# Voeding.net
KiCad netlist of a schematic drawn in Altium Designer
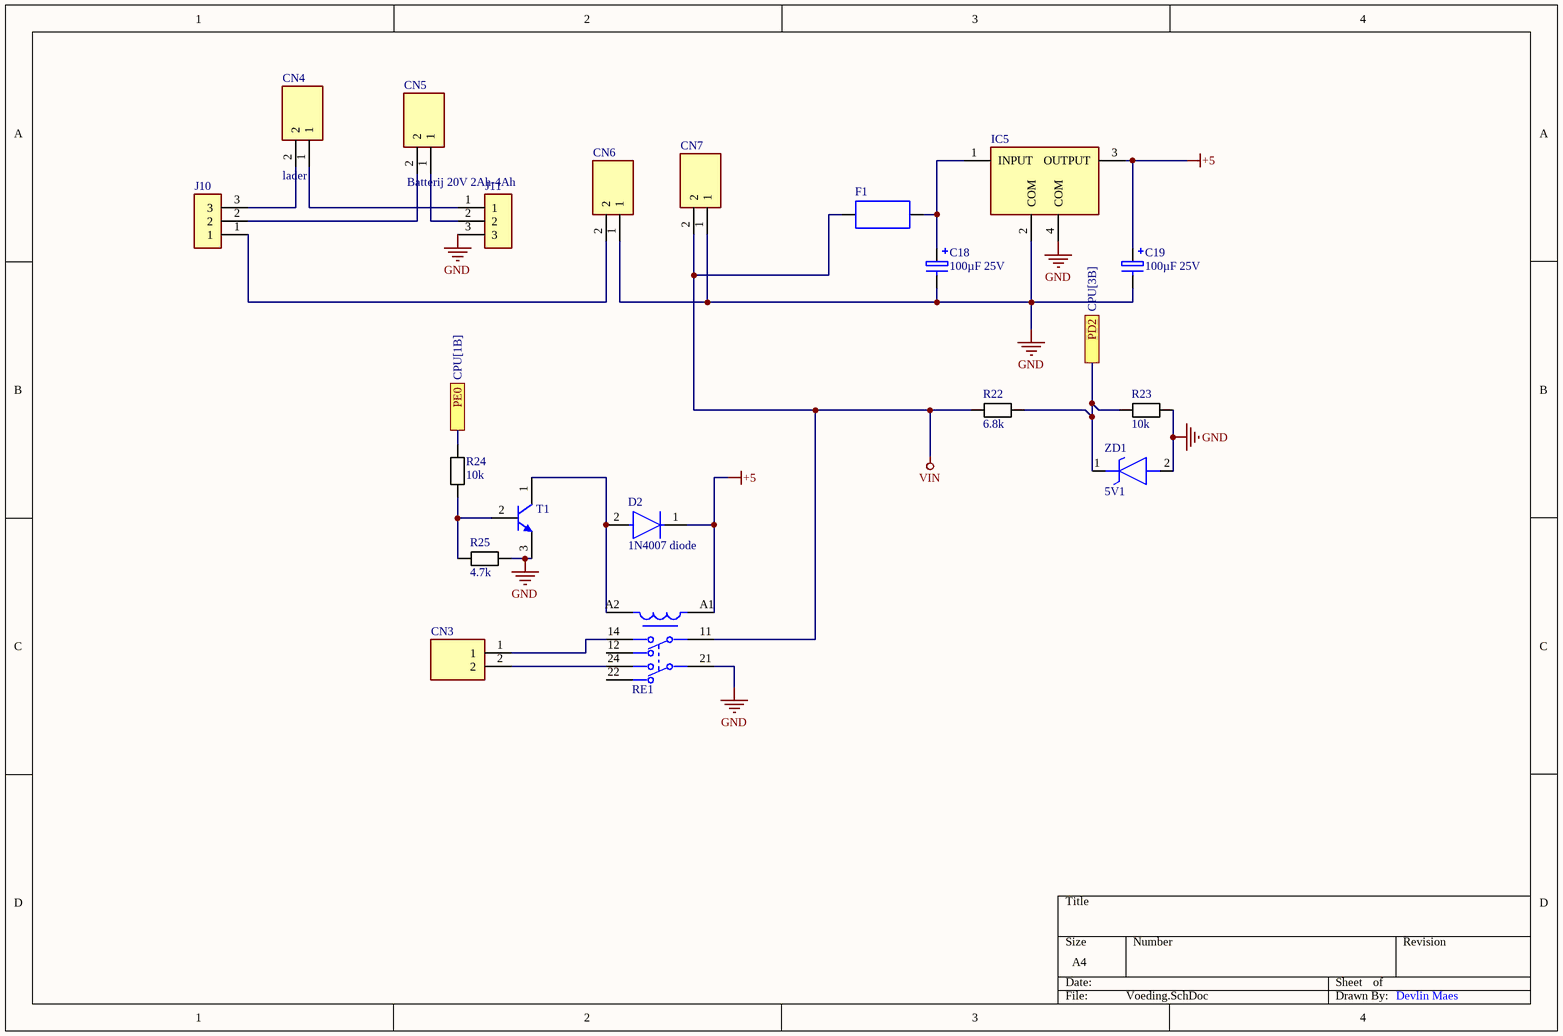
[diagram p0: Voeding.SchDoc]

(export (version "E")
  (design (tool "Eeschema 10.0.6"))
  (components
    (comp (ref "C18")
      (value "100µF 25V")
      (footprint "Elco 100uF 25V")
      (fields
        (field (name "PART NUMBER") "02015A270JAT2A")
        (field (name "MANUFACTURER") "AVX Interconnect / Elco")
      )
      (libsource (lib "schoolprojectcomponentlib") (part "Condensator Elco"))
    )
    (comp (ref "C19")
      (value "100µF 25V")
      (footprint "Elco 100uF 25V")
      (fields
        (field (name "PART NUMBER") "02015A270JAT2A")
        (field (name "MANUFACTURER") "AVX Interconnect / Elco")
      )
      (libsource (lib "schoolprojectcomponentlib") (part "Condensator Elco"))
    )
    (comp (ref "CN3")
      (value "282836-2")
      (footprint "Schroefconnector 2 Pin - duplicate")
      (description "Connector")
      (libsource (lib "schoolprojectcomponentlib") (part "Schroefconnector 2 Pin L"))
    )
    (comp (ref "CN4")
      (value "lader")
      (footprint "Schroefconnector 2 Pin - duplicate")
      (description "Connector")
      (fields (field (name "MANUFACTURER_PART_NUMBER") "282836-2"))
      (libsource (lib "") (part "Schroefconnector 2 Pin L_1"))
    )
    (comp (ref "CN5")
      (value "Batterij 20V 2Ah-4Ah")
      (footprint "Schroefconnector 2 Pin - duplicate")
      (description "Connector")
      (fields (field (name "MANUFACTURER_PART_NUMBER") "282836-2"))
      (libsource (lib "") (part "Schroefconnector 2 Pin L_1"))
    )
    (comp (ref "CN6")
      (value "282836-2")
      (footprint "Schroefconnector 2 Pin - duplicate")
      (description "Connector")
      (libsource (lib "") (part "Schroefconnector 2 Pin L_1"))
    )
    (comp (ref "CN7")
      (value "282836-2")
      (footprint "Schroefconnector 2 Pin - duplicate")
      (description "Connector")
      (libsource (lib "") (part "Schroefconnector 2 Pin L_1"))
    )
    (comp (ref "D2")
      (value "1N4007 diode")
      (footprint "1N4007(diode)")
      (description "Rectifier diode 1000 V 1 A DO-41, ,")
      (fields (field (name "MANUFACTURER PART NUMBER") "1N4007") (field (name "MANUFACTURER") "Diotec"))
      (libsource (lib "schoolprojectcomponentlib") (part "1N4007 diode"))
    )
    (comp (ref "F1")
      (value "~")
      (footprint "FuseHolder")
      (libsource (lib "schoolprojectcomponentlib") (part "FuseHolder"))
    )
    (comp (ref "IC5")
      (value "TL780-05CKTTR")
      (footprint "DC-DC Convertor")
      (description "IC REG LIN 5V 1.5A DDPAK/TO263-3")
      (libsource (lib "schoolprojectcomponentlib") (part "DC/DC Convertor"))
    )
    (comp (ref "J10")
      (value "5-146280-3")
      (footprint "3 Pin Header")
      (description "Connector 5-146280-3")
      (fields (field (name "MOUSER2 PART NUMBER") "571-5-146280-3"))
      (libsource (lib "schoolprojectcomponentlib") (part "3 Pin Header R"))
    )
    (comp (ref "J11")
      (value "5-146280-3")
      (footprint "3 Pin Header")
      (description "Connector 5-146280-3")
      (fields (field (name "MOUSER2 PART NUMBER") "571-5-146280-3"))
      (libsource (lib "") (part "3 Pin Header R_1"))
    )
    (comp (ref "R22")
      (value "6.8k")
      (footprint "weerstand")
      (fields (field (name "MANUFACTURER") "Vishay Dale") (field (name "PART NUMBER") "CRCW08050000Z0EA"))
      (libsource (lib "schoolprojectcomponentlib") (part "weerstand"))
    )
    (comp (ref "R23")
      (value "10k")
      (footprint "weerstand")
      (fields (field (name "MANUFACTURER") "Vishay Dale") (field (name "PART NUMBER") "CRCW08050000Z0EA"))
      (libsource (lib "schoolprojectcomponentlib") (part "weerstand"))
    )
    (comp (ref "R24")
      (value "10k")
      (footprint "weerstand")
      (fields (field (name "MANUFACTURER") "Vishay Dale") (field (name "PART NUMBER") "CRCW08050000Z0EA"))
      (libsource (lib "schoolprojectcomponentlib") (part "weerstand"))
    )
    (comp (ref "R25")
      (value "4.7k")
      (footprint "weerstand")
      (fields (field (name "MANUFACTURER") "Vishay Dale") (field (name "PART NUMBER") "CRCW08050000Z0EA"))
      (libsource (lib "schoolprojectcomponentlib") (part "weerstand"))
    )
    (comp (ref "RE1")
      (value "RT424005")
      (footprint "Relay RT424005")
      (description "RELAY GENERAL PURPOSE DPDT 8A 5V")
      (fields
        (field (name "OCTOPART") "https://octopart.com/5-1393243-9-te+connectivity-41835766")
        (field (name "MANUFACTURER") "TE Connectivity")
      )
      (libsource (lib "schoolprojectcomponentlib") (part "Relay"))
    )
    (comp (ref "T1")
      (value "BC547C")
      (footprint "BC547C (transistor)")
      (description "Amplifier Transistor, NPN Silicon, 3-Pin, 0,1A TO-92, Bulk Box")
      (fields (field (name "MANUFACTURER") "On Semiconductor"))
      (libsource (lib "schoolprojectcomponentlib") (part "BC547C"))
    )
    (comp (ref "ZD1")
      (value "5V1")
      (footprint "Zener diode")
      (description "Zener Diode")
      (fields
        (field (name "MOUSER2 PART NUMBER") "512-1N5231CTR")
        (field (name "MANUFACTURER_PART_NUMBER") "1N5231CTR")
      )
      (libsource (lib "schoolprojectcomponentlib") (part "Zenerdiode"))
    )
  )
  (nets
    (net (code "1") (name "+5") (class "Default")
      (node (ref "C19") (pin "1") (pinfunction "1_1") (pintype "passive"))
      (node (ref "D2") (pin "1") (pinfunction "C_1") (pintype "passive"))
      (node (ref "IC5") (pin "3") (pinfunction "OUTPUT_3") (pintype "power_in"))
      (node (ref "RE1") (pin "A1") (pinfunction "A1_A1") (pintype "passive"))
    )
    (net (code "2") (name "/PD2") (class "Default")
      (node (ref "R22") (pin "1") (pinfunction "1_1") (pintype "passive"))
      (node (ref "R23") (pin "2") (pinfunction "2_2") (pintype "passive"))
      (node (ref "ZD1") (pin "1") (pinfunction "K_1") (pintype "passive"))
    )
    (net (code "3") (name "/PE0") (class "Default")
      (node (ref "R24") (pin "2") (pinfunction "2_2") (pintype "passive"))
    )
    (net (code "4") (name "GND") (class "Default")
      (node (ref "C18") (pin "2") (pinfunction "2_2") (pintype "passive"))
      (node (ref "C19") (pin "2") (pinfunction "2_2") (pintype "passive"))
      (node (ref "CN6") (pin "1") (pinfunction "1_1") (pintype "passive"))
      (node (ref "CN7") (pin "1") (pinfunction "1_1") (pintype "passive"))
      (node (ref "IC5") (pin "2") (pinfunction "COM_2") (pintype "passive"))
      (node (ref "IC5") (pin "4") (pinfunction "COM_4") (pintype "passive"))
      (node (ref "J11") (pin "3") (pinfunction "3_3") (pintype "passive"))
      (node (ref "R23") (pin "1") (pinfunction "1_1") (pintype "passive"))
      (node (ref "R25") (pin "1") (pinfunction "1_1") (pintype "passive"))
      (node (ref "RE1") (pin "21") (pinfunction "21_21") (pintype "passive"))
      (node (ref "T1") (pin "3") (pinfunction "E_3") (pintype "passive"))
      (node (ref "ZD1") (pin "2") (pinfunction "A_2") (pintype "passive"))
    )
    (net (code "5") (name "Net-(CN3-Pad1)") (class "Default")
      (node (ref "CN3") (pin "1") (pinfunction "1_1") (pintype "passive"))
      (node (ref "RE1") (pin "14") (pinfunction "14_14") (pintype "passive"))
    )
    (net (code "6") (name "Net-(CN3-Pad2)") (class "Default")
      (node (ref "CN3") (pin "2") (pinfunction "2_2") (pintype "passive"))
      (node (ref "RE1") (pin "24") (pinfunction "24_24") (pintype "passive"))
    )
    (net (code "7") (name "Net-(CN4-Pad1)") (class "Default")
      (node (ref "CN4") (pin "1") (pinfunction "1_1") (pintype "passive"))
      (node (ref "J11") (pin "1") (pinfunction "1_1") (pintype "passive"))
    )
    (net (code "8") (name "Net-(CN4-Pad2)") (class "Default")
      (node (ref "CN4") (pin "2") (pinfunction "2_2") (pintype "passive"))
      (node (ref "J10") (pin "3") (pinfunction "3_3") (pintype "passive"))
    )
    (net (code "9") (name "Net-(CN5-Pad1)") (class "Default")
      (node (ref "CN5") (pin "1") (pinfunction "1_1") (pintype "passive"))
      (node (ref "J11") (pin "2") (pinfunction "2_2") (pintype "passive"))
    )
    (net (code "10") (name "Net-(CN5-Pad2)") (class "Default")
      (node (ref "CN5") (pin "2") (pinfunction "2_2") (pintype "passive"))
      (node (ref "J10") (pin "2") (pinfunction "2_2") (pintype "passive"))
    )
    (net (code "11") (name "Net-(CN6-Pad2)") (class "Default")
      (node (ref "CN6") (pin "2") (pinfunction "2_2") (pintype "passive"))
      (node (ref "J10") (pin "1") (pinfunction "1_1") (pintype "passive"))
    )
    (net (code "12") (name "Net-(D2-A)") (class "Default")
      (node (ref "D2") (pin "2") (pinfunction "A_2") (pintype "passive"))
      (node (ref "RE1") (pin "A2") (pinfunction "A2_A2") (pintype "passive"))
      (node (ref "T1") (pin "1") (pinfunction "C_1") (pintype "passive"))
    )
    (net (code "13") (name "Net-(IC5-INPUT)") (class "Default")
      (node (ref "C18") (pin "1") (pinfunction "1_1") (pintype "passive"))
      (node (ref "F1") (pin "2") (pinfunction "2_2") (pintype "passive"))
      (node (ref "IC5") (pin "1") (pinfunction "INPUT_1") (pintype "power_in"))
    )
    (net (code "14") (name "Net-(T1-B)") (class "Default")
      (node (ref "R24") (pin "1") (pinfunction "1_1") (pintype "passive"))
      (node (ref "R25") (pin "2") (pinfunction "2_2") (pintype "passive"))
      (node (ref "T1") (pin "2") (pinfunction "B_2") (pintype "passive"))
    )
    (net (code "15") (name "VIN") (class "Default")
      (node (ref "CN7") (pin "2") (pinfunction "2_2") (pintype "passive"))
      (node (ref "F1") (pin "1") (pinfunction "1_1") (pintype "passive"))
      (node (ref "R22") (pin "2") (pinfunction "2_2") (pintype "passive"))
      (node (ref "RE1") (pin "11") (pinfunction "11_11") (pintype "passive"))
    )
    (net (code "16") (name "unconnected-(RE1-Pad12)") (class "Default")
      (node (ref "RE1") (pin "12") (pinfunction "12_12") (pintype "passive"))
    )
    (net (code "17") (name "unconnected-(RE1-Pad22)") (class "Default")
      (node (ref "RE1") (pin "22") (pinfunction "22_22") (pintype "passive"))
    )
  )
)
